# LCD.net
KiCad netlist of a schematic drawn in Altium Designer
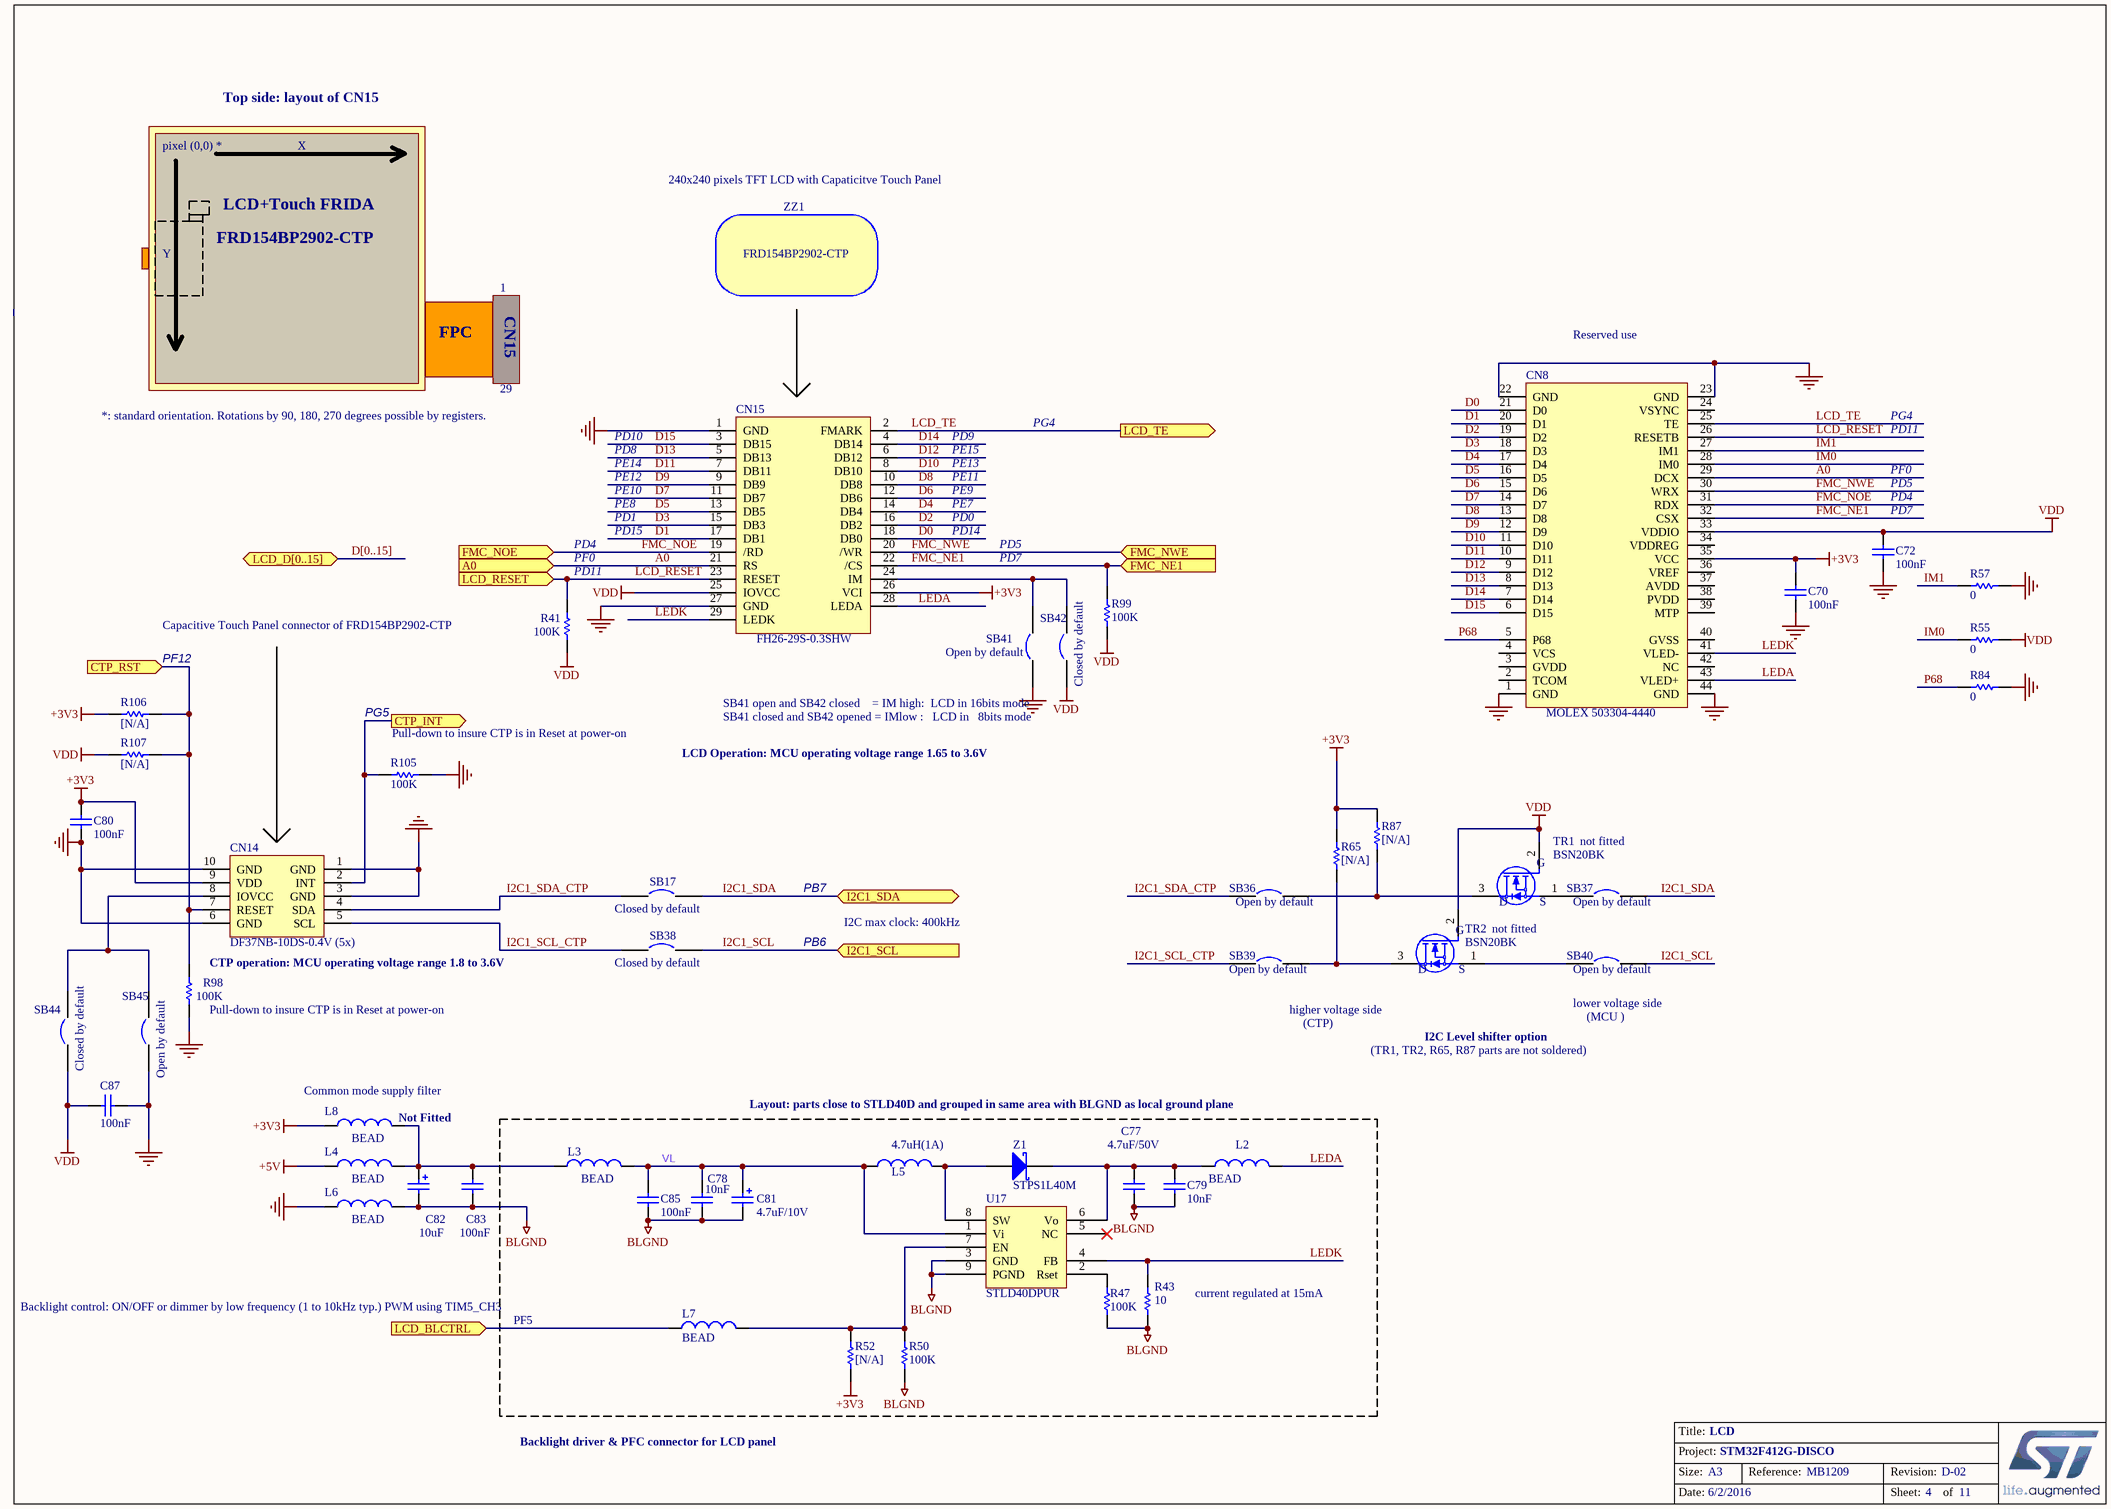
[diagram p0: LCD.SchDoc]

(export (version "E")
  (design (tool "Eeschema 10.0.6"))
  (components
    (comp (ref "C70")
      (value "100nF")
      (footprint "0402C")
      (description "Capacitor")
      (fields (field (name "PUBLISHER") "Altium Limited"))
      (libsource (lib "Miscellaneous Devices") (part "CAP"))
    )
    (comp (ref "C72")
      (value "100nF")
      (footprint "0402C")
      (description "Capacitor")
      (fields (field (name "PUBLISHER") "Altium Limited"))
      (libsource (lib "Miscellaneous Devices") (part "CAP"))
    )
    (comp (ref "C77")
      (value "4.7uF/50V")
      (footprint "1206C")
      (description "Capacitor")
      (fields (field (name "PUBLISHER") "Altium Limited"))
      (libsource (lib "Miscellaneous Devices") (part "CAP"))
    )
    (comp (ref "C78")
      (value "10nF")
      (footprint "0603C")
      (description "Capacitor")
      (fields (field (name "PUBLISHER") "Altium Limited"))
      (libsource (lib "Miscellaneous Devices") (part "CAP"))
    )
    (comp (ref "C79")
      (value "10nF")
      (footprint "0603C")
      (description "Capacitor")
      (fields (field (name "PUBLISHER") "Altium Limited"))
      (libsource (lib "*") (part "CAP"))
    )
    (comp (ref "C80")
      (value "100nF")
      (footprint "0402C")
      (description "Capacitor")
      (fields (field (name "PUBLISHER") "Altium Limited"))
      (libsource (lib "Miscellaneous Devices") (part "CAP"))
    )
    (comp (ref "C81")
      (value "4.7uF/10V")
      (footprint "1206C")
      (description "Polarized Capacitor (Radial)")
      (fields (field (name "PUBLISHER") "Altium Limited"))
      (libsource (lib "Miscellaneous Devices") (part "Cap Pol1"))
    )
    (comp (ref "C82")
      (value "10uF")
      (footprint "TAN-A")
      (description "Polarized Capacitor (Radial)")
      (fields (field (name "PUBLISHER") "Altium Limited"))
      (libsource (lib "Miscellaneous Devices") (part "Cap Pol1"))
    )
    (comp (ref "C83")
      (value "100nF")
      (footprint "0402C")
      (description "Capacitor")
      (fields (field (name "PUBLISHER") "Altium Limited"))
      (libsource (lib "Miscellaneous Devices") (part "Cap"))
    )
    (comp (ref "C85")
      (value "100nF")
      (footprint "0402C")
      (description "Capacitor")
      (fields (field (name "PUBLISHER") "Altium Limited"))
      (libsource (lib "Miscellaneous Devices") (part "CAP"))
    )
    (comp (ref "C87")
      (value "100nF")
      (footprint "0402C")
      (description "Capacitor")
      (fields (field (name "PUBLISHER") "Altium Limited"))
      (libsource (lib "Miscellaneous Devices") (part "CAP"))
    )
    (comp (ref "CN8")
      (value "MOLEX 503304-4440")
      (footprint "MOLEX_503304-4440")
      (description "LCD FCP BtoB receptacle")
      (libsource (lib "TinyMantaLP1MDisco") (part "MOLEX 503304-4410"))
    )
    (comp (ref "CN14")
      (value "DF37NB-10DS-0.4V (5x)")
      (footprint "DF37NB-10DS-0R4V")
      (description "Header, 5-Pin, Dual row")
      (fields (field (name "PUBLISHER") "Altium Limited"))
      (libsource (lib "MB1209") (part "Header 5X2A"))
    )
    (comp (ref "CN15")
      (value "FH26-29S-0.3SHW")
      (footprint "FH26-29S-0R3SHW")
      (description "29pins FPC connector")
      (libsource (lib "MB1209_3") (part "FH26-29S-0.3SHW"))
    )
    (comp (ref "L2")
      (value "BEAD")
      (footprint "0603L")
      (description "Inductor")
      (fields (field (name "PUBLISHER") "Altium Limited"))
      (libsource (lib "Miscellaneous Devices") (part "Inductor"))
    )
    (comp (ref "L3")
      (value "BEAD")
      (footprint "0603L")
      (description "Inductor")
      (fields (field (name "PUBLISHER") "Altium Limited"))
      (libsource (lib "Miscellaneous Devices") (part "Inductor"))
    )
    (comp (ref "L4")
      (value "BEAD")
      (footprint "0603L")
      (description "Inductor")
      (fields (field (name "PUBLISHER") "Altium Limited"))
      (libsource (lib "Miscellaneous Devices") (part "Inductor"))
    )
    (comp (ref "L5")
      (value "4.7uH(1A)")
      (footprint "1210L")
      (description "Inductor")
      (fields (field (name "PUBLISHER") "Altium Limited"))
      (libsource (lib "Miscellaneous Devices") (part "Inductor"))
    )
    (comp (ref "L6")
      (value "BEAD")
      (footprint "0603L")
      (description "Inductor")
      (fields (field (name "PUBLISHER") "Altium Limited"))
      (libsource (lib "Miscellaneous Devices") (part "Inductor"))
    )
    (comp (ref "L7")
      (value "BEAD")
      (footprint "0603L")
      (description "Inductor")
      (fields (field (name "PUBLISHER") "Altium Limited"))
      (libsource (lib "Miscellaneous Devices") (part "Inductor"))
    )
    (comp (ref "L8")
      (value "BEAD")
      (footprint "0603L")
      (description "Inductor")
      (fields (field (name "PUBLISHER") "Altium Limited"))
      (libsource (lib "Miscellaneous Devices") (part "Inductor"))
    )
    (comp (ref "R41")
      (value "100K")
      (footprint "0402R")
      (description "Resistor")
      (fields (field (name "PUBLISHER") "Altium Limited"))
      (libsource (lib "Miscellaneous Devices") (part "Res1"))
    )
    (comp (ref "R43")
      (value "10")
      (footprint "0603R")
      (description "Resistor")
      (fields (field (name "PUBLISHER") "Altium Limited"))
      (libsource (lib "Miscellaneous Devices") (part "Res1"))
    )
    (comp (ref "R47")
      (value "100K")
      (footprint "0402R")
      (description "Resistor")
      (fields (field (name "PUBLISHER") "Altium Limited"))
      (libsource (lib "Miscellaneous Devices") (part "Res1"))
    )
    (comp (ref "R50")
      (value "100K")
      (footprint "0402R")
      (description "Resistor")
      (fields (field (name "PUBLISHER") "Altium Limited"))
      (libsource (lib "Miscellaneous Devices") (part "Res1"))
    )
    (comp (ref "R52")
      (value "[N/A]")
      (footprint "0603R")
      (description "Resistor")
      (fields (field (name "PUBLISHER") "Altium Limited"))
      (libsource (lib "Miscellaneous Devices") (part "Res1"))
    )
    (comp (ref "R55")
      (value "0")
      (footprint "0402R")
      (description "Resistor")
      (fields (field (name "PUBLISHER") "Altium Limited"))
      (libsource (lib "Miscellaneous Devices") (part "Res1"))
    )
    (comp (ref "R57")
      (value "0")
      (footprint "0402R")
      (description "Resistor")
      (fields (field (name "PUBLISHER") "Altium Limited"))
      (libsource (lib "Miscellaneous Devices") (part "Res1"))
    )
    (comp (ref "R65")
      (value "[N/A]")
      (footprint "0603R")
      (description "Resistor")
      (fields (field (name "PUBLISHER") "Altium Limited"))
      (libsource (lib "") (part "Res1_1"))
    )
    (comp (ref "R84")
      (value "0")
      (footprint "0402R")
      (description "Resistor")
      (fields (field (name "PUBLISHER") "Altium Limited"))
      (libsource (lib "Miscellaneous Devices") (part "Res1"))
    )
    (comp (ref "R87")
      (value "[N/A]")
      (footprint "0603R")
      (description "Resistor")
      (fields (field (name "PUBLISHER") "Altium Limited"))
      (libsource (lib "") (part "Res1_1"))
    )
    (comp (ref "R98")
      (value "100K")
      (footprint "0402R")
      (description "Resistor")
      (fields (field (name "PUBLISHER") "Altium Limited"))
      (libsource (lib "Miscellaneous Devices") (part "res1"))
    )
    (comp (ref "R99")
      (value "100K")
      (footprint "0402R")
      (description "Resistor")
      (fields (field (name "PUBLISHER") "Altium Limited"))
      (libsource (lib "Miscellaneous Devices") (part "Res1"))
    )
    (comp (ref "R105")
      (value "100K")
      (footprint "0402R")
      (description "Resistor")
      (fields (field (name "PUBLISHER") "Altium Limited"))
      (libsource (lib "Miscellaneous Devices") (part "res1"))
    )
    (comp (ref "R106")
      (value "[N/A]")
      (footprint "0402R")
      (description "Resistor")
      (fields (field (name "PUBLISHER") "Altium Limited"))
      (libsource (lib "Miscellaneous Devices") (part "res1"))
    )
    (comp (ref "R107")
      (value "[N/A]")
      (footprint "0402R")
      (description "Resistor")
      (fields (field (name "PUBLISHER") "Altium Limited"))
      (libsource (lib "Miscellaneous Devices") (part "res1"))
    )
    (comp (ref "SB17")
      (value "Closed by default")
      (footprint "SB_0603")
      (description "Circuit Breaker")
      (fields (field (name "PUBLISHER") "Altium Limited"))
      (libsource (lib "Miscellaneous Devices") (part "Circuit Breaker"))
    )
    (comp (ref "SB36")
      (value "Open by default")
      (footprint "SB_0603")
      (description "Circuit Breaker")
      (fields (field (name "PUBLISHER") "Altium Limited"))
      (libsource (lib "Miscellaneous Devices") (part "Circuit Breaker"))
    )
    (comp (ref "SB37")
      (value "Open by default")
      (footprint "SB_0603")
      (description "Circuit Breaker")
      (fields (field (name "PUBLISHER") "Altium Limited"))
      (libsource (lib "Miscellaneous Devices") (part "Circuit Breaker"))
    )
    (comp (ref "SB38")
      (value "Closed by default")
      (footprint "SB_0603")
      (description "Circuit Breaker")
      (fields (field (name "PUBLISHER") "Altium Limited"))
      (libsource (lib "Miscellaneous Devices") (part "Circuit Breaker"))
    )
    (comp (ref "SB39")
      (value "Open by default")
      (footprint "SB_0603")
      (description "Circuit Breaker")
      (fields (field (name "PUBLISHER") "Altium Limited"))
      (libsource (lib "Miscellaneous Devices") (part "Circuit Breaker"))
    )
    (comp (ref "SB40")
      (value "Open by default")
      (footprint "SB_0603")
      (description "Circuit Breaker")
      (fields (field (name "PUBLISHER") "Altium Limited"))
      (libsource (lib "Miscellaneous Devices") (part "Circuit Breaker"))
    )
    (comp (ref "SB41")
      (value "Open by default")
      (footprint "SB_0603")
      (description "Circuit Breaker")
      (fields (field (name "PUBLISHER") "Altium Limited"))
      (libsource (lib "Miscellaneous Devices") (part "Circuit Breaker"))
    )
    (comp (ref "SB42")
      (value "Closed by default")
      (footprint "SB_0603")
      (description "Circuit Breaker")
      (fields (field (name "PUBLISHER") "Altium Limited"))
      (libsource (lib "Miscellaneous Devices") (part "Circuit Breaker"))
    )
    (comp (ref "SB44")
      (value "Closed by default")
      (footprint "SB_0603")
      (description "Circuit Breaker")
      (fields (field (name "PUBLISHER") "Altium Limited"))
      (libsource (lib "Miscellaneous Devices") (part "Circuit Breaker"))
    )
    (comp (ref "SB45")
      (value "Open by default")
      (footprint "SB_0603")
      (description "Circuit Breaker")
      (fields (field (name "PUBLISHER") "Altium Limited"))
      (libsource (lib "Miscellaneous Devices") (part "Circuit Breaker"))
    )
    (comp (ref "TR1") (value "BSN20BK") (footprint "SOT23-213") (libsource (lib "MB525") (part "2N7000")))
    (comp (ref "TR2") (value "BSN20BK") (footprint "SOT23-213") (libsource (lib "MB525") (part "2N7000")))
    (comp (ref "U17")
      (value "STLD40DPUR")
      (footprint "SON8_0R65_3X3")
      (libsource (lib "3.2LCD_daughterboard") (part "STLD40DPMR"))
    )
    (comp (ref "Z1")
      (value "STPS1L40M")
      (footprint "DO-216AA")
      (description "Schottky Diode")
      (fields (field (name "PUBLISHER") "Altium Limited"))
      (libsource (lib "Miscellaneous Devices") (part "D Schottky"))
    )
    (comp (ref "ZZ1") (value "FRD154BP2902-CTP") (libsource (lib "Almos") (part "BoM_Item")))
  )
  (nets
    (net (code "1") (name "+3V3") (class "Default")
      (node (ref "C70") (pin "1") (pinfunction "1_1") (pintype "passive"))
      (node (ref "C80") (pin "2") (pinfunction "2_2") (pintype "passive"))
      (node (ref "CN14") (pin "9") (pinfunction "VDD_9") (pintype "passive"))
      (node (ref "CN15") (pin "26") (pinfunction "VCI_26") (pintype "passive"))
      (node (ref "CN8") (pin "35") (pinfunction "VCC_35") (pintype "passive"))
      (node (ref "L8") (pin "1") (pinfunction "1_1") (pintype "passive"))
      (node (ref "R106") (pin "1") (pinfunction "1_1") (pintype "passive"))
      (node (ref "R52") (pin "1") (pinfunction "1_1") (pintype "passive"))
      (node (ref "R65") (pin "2") (pinfunction "2_2") (pintype "passive"))
      (node (ref "R87") (pin "2") (pinfunction "2_2") (pintype "passive"))
    )
    (net (code "2") (name "+5V") (class "Default")
      (node (ref "L4") (pin "1") (pinfunction "1_1") (pintype "passive"))
    )
    (net (code "3") (name "/A0") (class "Default")
      (node (ref "CN15") (pin "21") (pinfunction "RS_21") (pintype "passive"))
      (node (ref "CN8") (pin "29") (pinfunction "DCX_29") (pintype "passive"))
    )
    (net (code "4") (name "/CTP_INT") (class "Default")
      (node (ref "CN14") (pin "2") (pinfunction "INT_2") (pintype "passive"))
      (node (ref "R105") (pin "1") (pinfunction "1_1") (pintype "passive"))
    )
    (net (code "5") (name "/CTP_RST") (class "Default")
      (node (ref "CN14") (pin "7") (pinfunction "RESET_7") (pintype "passive"))
      (node (ref "R106") (pin "2") (pinfunction "2_2") (pintype "passive"))
      (node (ref "R107") (pin "2") (pinfunction "2_2") (pintype "passive"))
      (node (ref "R98") (pin "1") (pinfunction "1_1") (pintype "passive"))
    )
    (net (code "6") (name "/D0") (class "Default")
      (node (ref "CN15") (pin "18") (pinfunction "DB0_18") (pintype "passive"))
      (node (ref "CN8") (pin "21") (pinfunction "D0_21") (pintype "passive"))
    )
    (net (code "7") (name "/D1") (class "Default")
      (node (ref "CN15") (pin "17") (pinfunction "DB1_17") (pintype "passive"))
      (node (ref "CN8") (pin "20") (pinfunction "D1_20") (pintype "passive"))
    )
    (net (code "8") (name "/D2") (class "Default")
      (node (ref "CN15") (pin "16") (pinfunction "DB2_16") (pintype "passive"))
      (node (ref "CN8") (pin "19") (pinfunction "D2_19") (pintype "passive"))
    )
    (net (code "9") (name "/D3") (class "Default")
      (node (ref "CN15") (pin "15") (pinfunction "DB3_15") (pintype "passive"))
      (node (ref "CN8") (pin "18") (pinfunction "D3_18") (pintype "passive"))
    )
    (net (code "10") (name "/D4") (class "Default")
      (node (ref "CN15") (pin "14") (pinfunction "DB4_14") (pintype "passive"))
      (node (ref "CN8") (pin "17") (pinfunction "D4_17") (pintype "passive"))
    )
    (net (code "11") (name "/D5") (class "Default")
      (node (ref "CN15") (pin "13") (pinfunction "DB5_13") (pintype "passive"))
      (node (ref "CN8") (pin "16") (pinfunction "D5_16") (pintype "passive"))
    )
    (net (code "12") (name "/D6") (class "Default")
      (node (ref "CN15") (pin "12") (pinfunction "DB6_12") (pintype "passive"))
      (node (ref "CN8") (pin "15") (pinfunction "D6_15") (pintype "passive"))
    )
    (net (code "13") (name "/D7") (class "Default")
      (node (ref "CN15") (pin "11") (pinfunction "DB7_11") (pintype "passive"))
      (node (ref "CN8") (pin "14") (pinfunction "D7_14") (pintype "passive"))
    )
    (net (code "14") (name "/D8") (class "Default")
      (node (ref "CN15") (pin "10") (pinfunction "DB8_10") (pintype "passive"))
      (node (ref "CN8") (pin "13") (pinfunction "D8_13") (pintype "passive"))
    )
    (net (code "15") (name "/D9") (class "Default")
      (node (ref "CN15") (pin "9") (pinfunction "DB9_9") (pintype "passive"))
      (node (ref "CN8") (pin "12") (pinfunction "D9_12") (pintype "passive"))
    )
    (net (code "16") (name "/D10") (class "Default")
      (node (ref "CN15") (pin "8") (pinfunction "DB10_8") (pintype "passive"))
      (node (ref "CN8") (pin "11") (pinfunction "D10_11") (pintype "passive"))
    )
    (net (code "17") (name "/D11") (class "Default")
      (node (ref "CN15") (pin "7") (pinfunction "DB11_7") (pintype "passive"))
      (node (ref "CN8") (pin "10") (pinfunction "D11_10") (pintype "passive"))
    )
    (net (code "18") (name "/D12") (class "Default")
      (node (ref "CN15") (pin "6") (pinfunction "DB12_6") (pintype "passive"))
      (node (ref "CN8") (pin "9") (pinfunction "D12_9") (pintype "passive"))
    )
    (net (code "19") (name "/D13") (class "Default")
      (node (ref "CN15") (pin "5") (pinfunction "DB13_5") (pintype "passive"))
      (node (ref "CN8") (pin "8") (pinfunction "D13_8") (pintype "passive"))
    )
    (net (code "20") (name "/D14") (class "Default")
      (node (ref "CN15") (pin "4") (pinfunction "DB14_4") (pintype "passive"))
      (node (ref "CN8") (pin "7") (pinfunction "D14_7") (pintype "passive"))
    )
    (net (code "21") (name "/D15") (class "Default")
      (node (ref "CN15") (pin "3") (pinfunction "DB15_3") (pintype "passive"))
      (node (ref "CN8") (pin "6") (pinfunction "D15_6") (pintype "passive"))
    )
    (net (code "23") (name "/FMC_NE1") (class "Default")
      (node (ref "CN15") (pin "22") (pinfunction "/CS_22") (pintype "passive"))
      (node (ref "CN8") (pin "32") (pinfunction "CSX_32") (pintype "passive"))
      (node (ref "R99") (pin "1") (pinfunction "1_1") (pintype "passive"))
    )
    (net (code "24") (name "/FMC_NOE") (class "Default")
      (node (ref "CN15") (pin "19") (pinfunction "/RD_19") (pintype "passive"))
      (node (ref "CN8") (pin "31") (pinfunction "RDX_31") (pintype "passive"))
    )
    (net (code "25") (name "/FMC_NWE") (class "Default")
      (node (ref "CN15") (pin "20") (pinfunction "/WR_20") (pintype "passive"))
      (node (ref "CN8") (pin "30") (pinfunction "WRX_30") (pintype "passive"))
    )
    (net (code "26") (name "/I2C1_SCL") (class "Default")
      (node (ref "SB38") (pin "2") (pinfunction "2_2") (pintype "passive"))
      (node (ref "SB40") (pin "2") (pinfunction "2_2") (pintype "passive"))
    )
    (net (code "27") (name "/I2C1_SCL_CTP") (class "Default")
      (node (ref "CN14") (pin "5") (pinfunction "SCL_5") (pintype "passive"))
      (node (ref "SB38") (pin "1") (pinfunction "1_1") (pintype "passive"))
      (node (ref "SB39") (pin "1") (pinfunction "1_1") (pintype "passive"))
    )
    (net (code "28") (name "/I2C1_SDA") (class "Default")
      (node (ref "SB17") (pin "2") (pinfunction "2_2") (pintype "passive"))
      (node (ref "SB37") (pin "2") (pinfunction "2_2") (pintype "passive"))
    )
    (net (code "29") (name "/I2C1_SDA_CTP") (class "Default")
      (node (ref "CN14") (pin "4") (pinfunction "SDA_4") (pintype "passive"))
      (node (ref "SB17") (pin "1") (pinfunction "1_1") (pintype "passive"))
      (node (ref "SB36") (pin "1") (pinfunction "1_1") (pintype "passive"))
    )
    (net (code "30") (name "/IM0") (class "Default")
      (node (ref "CN8") (pin "28") (pinfunction "IM0_28") (pintype "passive"))
      (node (ref "R55") (pin "2") (pinfunction "2_2") (pintype "passive"))
    )
    (net (code "31") (name "/IM1") (class "Default")
      (node (ref "CN8") (pin "27") (pinfunction "IM1_27") (pintype "passive"))
      (node (ref "R57") (pin "2") (pinfunction "2_2") (pintype "passive"))
    )
    (net (code "32") (name "/LCD_BLCTRL") (class "Default")
      (node (ref "L7") (pin "1") (pinfunction "1_1") (pintype "passive"))
    )
    (net (code "33") (name "/LCD_RESET") (class "Default")
      (node (ref "CN15") (pin "23") (pinfunction "RESET_23") (pintype "passive"))
      (node (ref "CN8") (pin "26") (pinfunction "RESETB_26") (pintype "passive"))
      (node (ref "R41") (pin "2") (pinfunction "2_2") (pintype "passive"))
    )
    (net (code "34") (name "/LCD_TE") (class "Default")
      (node (ref "CN15") (pin "2") (pinfunction "FMARK_2") (pintype "passive"))
      (node (ref "CN8") (pin "25") (pinfunction "TE_25") (pintype "passive"))
    )
    (net (code "35") (name "/LEDA") (class "Default")
      (node (ref "CN15") (pin "28") (pinfunction "LEDA_28") (pintype "passive"))
      (node (ref "CN8") (pin "43") (pinfunction "VLED+_43") (pintype "passive"))
      (node (ref "L2") (pin "2") (pinfunction "2_2") (pintype "passive"))
    )
    (net (code "36") (name "/LEDK") (class "Default")
      (node (ref "CN15") (pin "29") (pinfunction "LEDK_29") (pintype "passive"))
      (node (ref "CN8") (pin "41") (pinfunction "VLED-_41") (pintype "passive"))
      (node (ref "R43") (pin "2") (pinfunction "2_2") (pintype "passive"))
      (node (ref "U17") (pin "4") (pinfunction "FB_4") (pintype "passive"))
    )
    (net (code "37") (name "/P68") (class "Default")
      (node (ref "CN8") (pin "5") (pinfunction "P68_5") (pintype "passive"))
      (node (ref "R84") (pin "2") (pinfunction "2_2") (pintype "passive"))
    )
    (net (code "38") (name "/VL") (class "Default")
      (node (ref "C78") (pin "2") (pinfunction "2_2") (pintype "passive"))
      (node (ref "C81") (pin "1") (pinfunction "1_1") (pintype "passive"))
      (node (ref "C85") (pin "2") (pinfunction "2_2") (pintype "passive"))
      (node (ref "L3") (pin "2") (pinfunction "2_2") (pintype "passive"))
      (node (ref "L5") (pin "1") (pinfunction "1_1") (pintype "passive"))
      (node (ref "U17") (pin "1") (pinfunction "Vi_1") (pintype "passive"))
    )
    (net (code "39") (name "BLGND") (class "Default")
      (node (ref "C77") (pin "2") (pinfunction "2_2") (pintype "passive"))
      (node (ref "C78") (pin "1") (pinfunction "1_1") (pintype "passive"))
      (node (ref "C79") (pin "1") (pinfunction "1_1") (pintype "passive"))
      (node (ref "C81") (pin "2") (pinfunction "2_2") (pintype "passive"))
      (node (ref "C82") (pin "2") (pinfunction "2_2") (pintype "passive"))
      (node (ref "C83") (pin "2") (pinfunction "2_2") (pintype "passive"))
      (node (ref "C85") (pin "1") (pinfunction "1_1") (pintype "passive"))
      (node (ref "L6") (pin "2") (pinfunction "2_2") (pintype "passive"))
      (node (ref "R43") (pin "1") (pinfunction "1_1") (pintype "passive"))
      (node (ref "R47") (pin "2") (pinfunction "2_2") (pintype "passive"))
      (node (ref "R50") (pin "1") (pinfunction "1_1") (pintype "passive"))
      (node (ref "U17") (pin "3") (pinfunction "GND_3") (pintype "passive"))
      (node (ref "U17") (pin "9") (pinfunction "PGND_9") (pintype "passive"))
    )
    (net (code "40") (name "GND") (class "Default")
      (node (ref "C70") (pin "2") (pinfunction "2_2") (pintype "passive"))
      (node (ref "C72") (pin "2") (pinfunction "2_2") (pintype "passive"))
      (node (ref "C80") (pin "1") (pinfunction "1_1") (pintype "passive"))
      (node (ref "C87") (pin "1") (pinfunction "1_1") (pintype "passive"))
      (node (ref "CN14") (pin "1") (pinfunction "GND_1") (pintype "passive"))
      (node (ref "CN14") (pin "10") (pinfunction "GND_10") (pintype "passive"))
      (node (ref "CN14") (pin "3") (pinfunction "GND_3") (pintype "passive"))
      (node (ref "CN14") (pin "6") (pinfunction "GND_6") (pintype "passive"))
      (node (ref "CN15") (pin "1") (pinfunction "GND_1") (pintype "passive"))
      (node (ref "CN15") (pin "27") (pinfunction "GND_27") (pintype "passive"))
      (node (ref "CN8") (pin "1") (pinfunction "GND_1") (pintype "passive"))
      (node (ref "CN8") (pin "22") (pinfunction "GND_22") (pintype "passive"))
      (node (ref "CN8") (pin "23") (pinfunction "GND_23") (pintype "passive"))
      (node (ref "CN8") (pin "44") (pinfunction "GND_44") (pintype "passive"))
      (node (ref "L6") (pin "1") (pinfunction "1_1") (pintype "passive"))
      (node (ref "R105") (pin "2") (pinfunction "2_2") (pintype "passive"))
      (node (ref "R57") (pin "1") (pinfunction "1_1") (pintype "passive"))
      (node (ref "R84") (pin "1") (pinfunction "1_1") (pintype "passive"))
      (node (ref "R98") (pin "2") (pinfunction "2_2") (pintype "passive"))
      (node (ref "SB41") (pin "1") (pinfunction "1_1") (pintype "passive"))
      (node (ref "SB45") (pin "1") (pinfunction "1_1") (pintype "passive"))
    )
    (net (code "41") (name "Net-(C82-Pad1)") (class "Default")
      (node (ref "C82") (pin "1") (pinfunction "1_1") (pintype "passive"))
      (node (ref "C83") (pin "1") (pinfunction "1_1") (pintype "passive"))
      (node (ref "L3") (pin "1") (pinfunction "1_1") (pintype "passive"))
      (node (ref "L4") (pin "2") (pinfunction "2_2") (pintype "passive"))
      (node (ref "L8") (pin "2") (pinfunction "2_2") (pintype "passive"))
    )
    (net (code "42") (name "Net-(CN14-IOVCC)") (class "Default")
      (node (ref "CN14") (pin "8") (pinfunction "IOVCC_8") (pintype "passive"))
      (node (ref "SB44") (pin "2") (pinfunction "2_2") (pintype "passive"))
      (node (ref "SB45") (pin "2") (pinfunction "2_2") (pintype "passive"))
    )
    (net (code "43") (name "Net-(CN15-IM)") (class "Default")
      (node (ref "CN15") (pin "24") (pinfunction "IM_24") (pintype "passive"))
      (node (ref "SB41") (pin "2") (pinfunction "2_2") (pintype "passive"))
      (node (ref "SB42") (pin "2") (pinfunction "2_2") (pintype "passive"))
    )
    (net (code "44") (name "Net-(TR1-D)") (class "Default")
      (node (ref "R87") (pin "1") (pinfunction "1_1") (pintype "passive"))
      (node (ref "SB36") (pin "2") (pinfunction "2_2") (pintype "passive"))
      (node (ref "TR1") (pin "3") (pinfunction "D_3") (pintype "passive"))
    )
    (net (code "45") (name "Net-(TR1-S)") (class "Default")
      (node (ref "SB37") (pin "1") (pinfunction "1_1") (pintype "passive"))
      (node (ref "TR1") (pin "1") (pinfunction "S_1") (pintype "passive"))
    )
    (net (code "46") (name "Net-(TR2-D)") (class "Default")
      (node (ref "R65") (pin "1") (pinfunction "1_1") (pintype "passive"))
      (node (ref "SB39") (pin "2") (pinfunction "2_2") (pintype "passive"))
      (node (ref "TR2") (pin "3") (pinfunction "D_3") (pintype "passive"))
    )
    (net (code "47") (name "Net-(TR2-S)") (class "Default")
      (node (ref "SB40") (pin "1") (pinfunction "1_1") (pintype "passive"))
      (node (ref "TR2") (pin "1") (pinfunction "S_1") (pintype "passive"))
    )
    (net (code "48") (name "Net-(U17-EN)") (class "Default")
      (node (ref "L7") (pin "2") (pinfunction "2_2") (pintype "passive"))
      (node (ref "R50") (pin "2") (pinfunction "2_2") (pintype "passive"))
      (node (ref "R52") (pin "2") (pinfunction "2_2") (pintype "passive"))
      (node (ref "U17") (pin "7") (pinfunction "EN_7") (pintype "passive"))
    )
    (net (code "49") (name "Net-(U17-Rset)") (class "Default")
      (node (ref "R47") (pin "1") (pinfunction "1_1") (pintype "passive"))
      (node (ref "U17") (pin "2") (pinfunction "Rset_2") (pintype "passive"))
    )
    (net (code "50") (name "Net-(U17-SW)") (class "Default")
      (node (ref "L5") (pin "2") (pinfunction "2_2") (pintype "passive"))
      (node (ref "U17") (pin "8") (pinfunction "SW_8") (pintype "passive"))
      (node (ref "Z1") (pin "1") (pinfunction "A_1") (pintype "passive"))
    )
    (net (code "51") (name "Net-(U17-Vo)") (class "Default")
      (node (ref "C77") (pin "1") (pinfunction "1_1") (pintype "passive"))
      (node (ref "C79") (pin "2") (pinfunction "2_2") (pintype "passive"))
      (node (ref "L2") (pin "1") (pinfunction "1_1") (pintype "passive"))
      (node (ref "U17") (pin "6") (pinfunction "Vo_6") (pintype "passive"))
      (node (ref "Z1") (pin "2") (pinfunction "K_2") (pintype "passive"))
    )
    (net (code "52") (name "VDD") (class "Default")
      (node (ref "C72") (pin "1") (pinfunction "1_1") (pintype "passive"))
      (node (ref "C87") (pin "2") (pinfunction "2_2") (pintype "passive"))
      (node (ref "CN15") (pin "25") (pinfunction "IOVCC_25") (pintype "passive"))
      (node (ref "CN8") (pin "33") (pinfunction "VDDIO_33") (pintype "passive"))
      (node (ref "R107") (pin "1") (pinfunction "1_1") (pintype "passive"))
      (node (ref "R41") (pin "1") (pinfunction "1_1") (pintype "passive"))
      (node (ref "R55") (pin "1") (pinfunction "1_1") (pintype "passive"))
      (node (ref "R99") (pin "2") (pinfunction "2_2") (pintype "passive"))
      (node (ref "SB42") (pin "1") (pinfunction "1_1") (pintype "passive"))
      (node (ref "SB44") (pin "1") (pinfunction "1_1") (pintype "passive"))
      (node (ref "TR1") (pin "2") (pinfunction "G_2") (pintype "passive"))
      (node (ref "TR2") (pin "2") (pinfunction "G_2") (pintype "passive"))
    )
    (net (code "53") (name "unconnected-(CN8-AVDD-Pad37)") (class "Default")
      (node (ref "CN8") (pin "37") (pinfunction "AVDD_37") (pintype "passive"))
    )
    (net (code "54") (name "unconnected-(CN8-GVDD-Pad3)") (class "Default")
      (node (ref "CN8") (pin "3") (pinfunction "GVDD_3") (pintype "passive"))
    )
    (net (code "55") (name "unconnected-(CN8-GVSS-Pad40)") (class "Default")
      (node (ref "CN8") (pin "40") (pinfunction "GVSS_40") (pintype "passive"))
    )
    (net (code "56") (name "unconnected-(CN8-MTP-Pad39)") (class "Default")
      (node (ref "CN8") (pin "39") (pinfunction "MTP_39") (pintype "passive"))
    )
    (net (code "57") (name "unconnected-(CN8-NC-Pad42)") (class "Default")
      (node (ref "CN8") (pin "42") (pinfunction "NC_42") (pintype "passive"))
    )
    (net (code "58") (name "unconnected-(CN8-PVDD-Pad38)") (class "Default")
      (node (ref "CN8") (pin "38") (pinfunction "PVDD_38") (pintype "passive"))
    )
    (net (code "59") (name "unconnected-(CN8-TCOM-Pad2)") (class "Default")
      (node (ref "CN8") (pin "2") (pinfunction "TCOM_2") (pintype "passive"))
    )
    (net (code "60") (name "unconnected-(CN8-VCS-Pad4)") (class "Default")
      (node (ref "CN8") (pin "4") (pinfunction "VCS_4") (pintype "passive"))
    )
    (net (code "61") (name "unconnected-(CN8-VDDREG-Pad34)") (class "Default")
      (node (ref "CN8") (pin "34") (pinfunction "VDDREG_34") (pintype "passive"))
    )
    (net (code "62") (name "unconnected-(CN8-VREF-Pad36)") (class "Default")
      (node (ref "CN8") (pin "36") (pinfunction "VREF_36") (pintype "passive"))
    )
    (net (code "63") (name "unconnected-(CN8-VSYNC-Pad24)") (class "Default")
      (node (ref "CN8") (pin "24") (pinfunction "VSYNC_24") (pintype "passive"))
    )
    (net (code "64") (name "unconnected-(U17-NC-Pad5)") (class "Default")
      (node (ref "U17") (pin "5") (pinfunction "NC_5") (pintype "passive+no_connect"))
    )
  )
)
